# 0HP_AND_Gate_REV_1.net
KiCad netlist of a schematic drawn in EAGLE
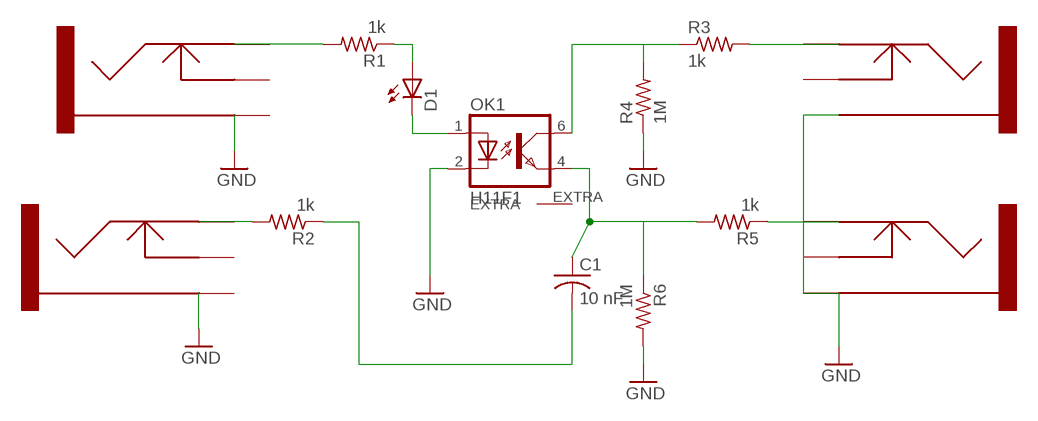
[diagram p0: schematic, sheet 1]

(export (version "E")
  (design (tool "Eeschema 10.0.6"))
  (components
    (comp (ref "C1")
      (value "10 nF")
      (footprint "eagle-import:C025-024X044")
      (libsource (lib "eagle-import") (part "C-US025-024X044"))
    )
    (comp (ref "CV1")
      (value "3.5MMJACK")
      (footprint "eagle-import:3.5MMPHONEJACK")
      (libsource (lib "eagle-import") (part "3.5MMJACK"))
    )
    (comp (ref "CV2")
      (value "3.5MMJACK")
      (footprint "eagle-import:3.5MMPHONEJACK")
      (libsource (lib "eagle-import") (part "3.5MMJACK"))
    )
    (comp (ref "D1")
      (value "LED3MM")
      (footprint "eagle-import:LED3MM")
      (libsource (lib "eagle-import") (part "LED3MM"))
    )
    (comp (ref "IN")
      (value "3.5MMJACK")
      (footprint "eagle-import:3.5MMPHONEJACK")
      (libsource (lib "eagle-import") (part "3.5MMJACK"))
    )
    (comp (ref "OK1")
      (value "H11F1")
      (footprint "eagle-import:DIL05")
      (libsource (lib "eagle-import") (part "H11F1"))
    )
    (comp (ref "OUT")
      (value "3.5MMJACK")
      (footprint "eagle-import:3.5MMPHONEJACK")
      (libsource (lib "eagle-import") (part "3.5MMJACK"))
    )
    (comp (ref "R1")
      (value "1k")
      (footprint "eagle-import:0207_2V")
      (libsource (lib "eagle-import") (part "R-US_0207/2V"))
    )
    (comp (ref "R2")
      (value "1k")
      (footprint "eagle-import:0207_2V")
      (libsource (lib "eagle-import") (part "R-US_0207/2V"))
    )
    (comp (ref "R3")
      (value "1k")
      (footprint "eagle-import:0207_2V")
      (libsource (lib "eagle-import") (part "R-US_0207/2V"))
    )
    (comp (ref "R4")
      (value "1M")
      (footprint "eagle-import:0207_2V")
      (libsource (lib "eagle-import") (part "R-US_0207/2V"))
    )
    (comp (ref "R5")
      (value "1k")
      (footprint "eagle-import:0207_2V")
      (libsource (lib "eagle-import") (part "R-US_0207/2V"))
    )
    (comp (ref "R6")
      (value "1M")
      (footprint "eagle-import:0207_2V")
      (libsource (lib "eagle-import") (part "R-US_0207/2V"))
    )
  )
  (nets
    (net (code "1") (name "GND") (class "Default")
      (node (ref "CV1") (pin "SLEEVE") (pinfunction "SLEEVE_SLEEVE") (pintype "bidirectional"))
      (node (ref "CV2") (pin "SLEEVE") (pinfunction "SLEEVE_SLEEVE") (pintype "bidirectional"))
      (node (ref "IN") (pin "SLEEVE") (pinfunction "SLEEVE_SLEEVE") (pintype "bidirectional"))
      (node (ref "OK1") (pin "2") (pinfunction "C_2") (pintype "passive"))
      (node (ref "OUT") (pin "SLEEVE") (pinfunction "SLEEVE_SLEEVE") (pintype "bidirectional"))
      (node (ref "R4") (pin "1") (pinfunction "1_1") (pintype "passive"))
      (node (ref "R6") (pin "2") (pinfunction "2_2") (pintype "passive"))
    )
    (net (code "2") (name "Net-(C1-Pad2)") (class "Default")
      (node (ref "C1") (pin "2") (pinfunction "2_2") (pintype "passive"))
      (node (ref "R2") (pin "1") (pinfunction "1_1") (pintype "passive"))
    )
    (net (code "3") (name "Net-(CV1-PadTIP)") (class "Default")
      (node (ref "CV1") (pin "TIP") (pinfunction "TIP_TIP") (pintype "bidirectional"))
      (node (ref "R2") (pin "2") (pinfunction "2_2") (pintype "passive"))
    )
    (net (code "4") (name "Net-(CV2-PadTIP)") (class "Default")
      (node (ref "CV2") (pin "TIP") (pinfunction "TIP_TIP") (pintype "bidirectional"))
      (node (ref "R1") (pin "2") (pinfunction "2_2") (pintype "passive"))
    )
    (net (code "5") (name "Net-(D1-C)") (class "Default")
      (node (ref "D1") (pin "K") (pinfunction "C_K") (pintype "passive"))
      (node (ref "OK1") (pin "1") (pinfunction "A_1") (pintype "passive"))
    )
    (net (code "6") (name "Net-(D1-PadA)") (class "Default")
      (node (ref "D1") (pin "A") (pinfunction "A_A") (pintype "passive"))
      (node (ref "R1") (pin "1") (pinfunction "1_1") (pintype "passive"))
    )
    (net (code "7") (name "Net-(IN-PadTIP)") (class "Default")
      (node (ref "IN") (pin "TIP") (pinfunction "TIP_TIP") (pintype "bidirectional"))
      (node (ref "R5") (pin "1") (pinfunction "1_1") (pintype "passive"))
    )
    (net (code "8") (name "Net-(OK1-COL)") (class "Default")
      (node (ref "OK1") (pin "6") (pinfunction "COL_6") (pintype "passive"))
      (node (ref "R3") (pin "1") (pinfunction "1_1") (pintype "passive"))
      (node (ref "R4") (pin "2") (pinfunction "2_2") (pintype "passive"))
    )
    (net (code "9") (name "Net-(OK1-EMIT)") (class "Default")
      (node (ref "C1") (pin "1") (pinfunction "1_1") (pintype "passive"))
      (node (ref "OK1") (pin "4") (pinfunction "EMIT_4") (pintype "passive"))
      (node (ref "R5") (pin "2") (pinfunction "2_2") (pintype "passive"))
      (node (ref "R6") (pin "1") (pinfunction "1_1") (pintype "passive"))
    )
    (net (code "10") (name "Net-(OUT-PadTIP)") (class "Default")
      (node (ref "OUT") (pin "TIP") (pinfunction "TIP_TIP") (pintype "bidirectional"))
      (node (ref "R3") (pin "2") (pinfunction "2_2") (pintype "passive"))
    )
    (net (code "11") (name "unconnected-(CV1-PadSWITCH)") (class "Default")
      (node (ref "CV1") (pin "SWITCH") (pinfunction "SWITCH_SWITCH") (pintype "bidirectional"))
    )
    (net (code "12") (name "unconnected-(CV2-PadSWITCH)") (class "Default")
      (node (ref "CV2") (pin "SWITCH") (pinfunction "SWITCH_SWITCH") (pintype "bidirectional"))
    )
    (net (code "13") (name "unconnected-(IN-PadSWITCH)") (class "Default")
      (node (ref "IN") (pin "SWITCH") (pinfunction "SWITCH_SWITCH") (pintype "bidirectional"))
    )
    (net (code "14") (name "unconnected-(OK1-PadEXTRA)") (class "Default")
      (node (ref "OK1") (pin "EXTRA") (pinfunction "EXTRA_EXTRA") (pintype "bidirectional"))
    )
    (net (code "15") (name "unconnected-(OUT-PadSWITCH)") (class "Default")
      (node (ref "OUT") (pin "SWITCH") (pinfunction "SWITCH_SWITCH") (pintype "bidirectional"))
    )
  )
)
